# ESP8266.net
KiCad netlist of a schematic drawn in Altium Designer
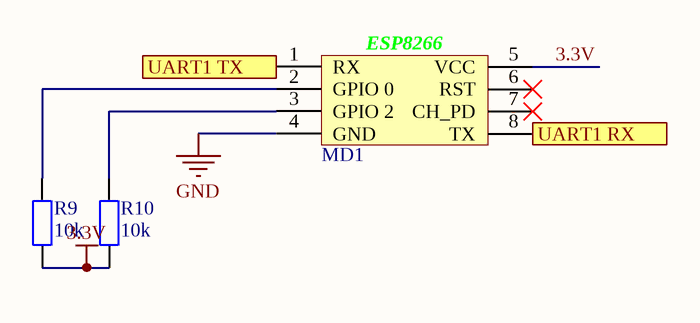
[diagram p0: ESP8266.SchDoc]

(export (version "E")
  (design (tool "Eeschema 10.0.6"))
  (components
    (comp (ref "MD1")
      (value "ESP8266 Module")
      (footprint "ESP2866 Module")
      (libsource (lib "Altium_Lib_by_KhueNguyenCreator") (part "ESP8266 Module"))
    )
    (comp (ref "R9")
      (value "10k")
      (footprint "tro smd 0805")
      (description "Dán")
      (libsource (lib "Altium_Lib_by_KhueNguyenCreator") (part "Tro 0805 5% 10k"))
    )
    (comp (ref "R10")
      (value "10k")
      (footprint "tro smd 0805")
      (description "Dán")
      (libsource (lib "Altium_Lib_by_KhueNguyenCreator") (part "Tro 0805 5% 10k"))
    )
  )
  (nets
    (net (code "1") (name "/UART1 RX") (class "Default")
      (node (ref "MD1") (pin "8") (pinfunction "TX_8") (pintype "passive"))
    )
    (net (code "2") (name "/UART1 TX") (class "Default")
      (node (ref "MD1") (pin "1") (pinfunction "RX_1") (pintype "passive"))
    )
    (net (code "3") (name "3.3V") (class "Default")
      (node (ref "MD1") (pin "5") (pinfunction "VCC_5") (pintype "passive"))
      (node (ref "R10") (pin "1") (pinfunction "1_1") (pintype "passive"))
      (node (ref "R9") (pin "1") (pinfunction "1_1") (pintype "passive"))
    )
    (net (code "4") (name "GND") (class "Default")
      (node (ref "MD1") (pin "4") (pinfunction "GND_4") (pintype "passive"))
    )
    (net (code "5") (name "Net-(MD1-GPIO_0)") (class "Default")
      (node (ref "MD1") (pin "2") (pinfunction "GPIO_0_2") (pintype "passive"))
      (node (ref "R9") (pin "2") (pinfunction "2_2") (pintype "passive"))
    )
    (net (code "6") (name "Net-(MD1-GPIO_2)") (class "Default")
      (node (ref "MD1") (pin "3") (pinfunction "GPIO_2_3") (pintype "passive"))
      (node (ref "R10") (pin "2") (pinfunction "2_2") (pintype "passive"))
    )
    (net (code "7") (name "unconnected-(MD1-CH_PD-Pad7)") (class "Default")
      (node (ref "MD1") (pin "7") (pinfunction "CH_PD_7") (pintype "passive+no_connect"))
    )
    (net (code "8") (name "unconnected-(MD1-RST-Pad6)") (class "Default")
      (node (ref "MD1") (pin "6") (pinfunction "RST_6") (pintype "passive+no_connect"))
    )
  )
)
